# ADCIN_ACcoupled_TCM1-83X.net
KiCad netlist of a schematic drawn in Altium Designer
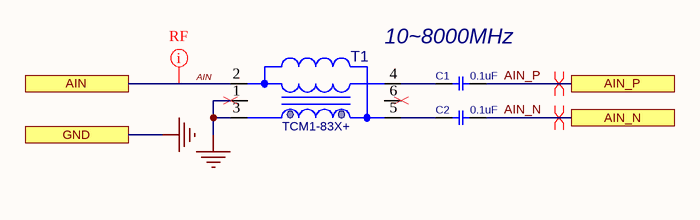
[diagram p0: ADCIN_ACcoupled_TCM1-83X+.SchDoc]

(export (version "E")
  (design (tool "Eeschema 10.0.6"))
  (components
    (comp (ref "C1")
      (value "0.1uF")
      (footprint "C0402")
      (description "CAP, MLCC, 100nF, 50V, X7R, 10%, 0402C")
      (fields (field (name "MANF_P#") "UMK105B7104KVHF") (field (name "MANF") "Taiyo Yuden"))
      (libsource (lib "mlcc_smd_passive") (part "CAP_SMD_MLCC_100n50T"))
    )
    (comp (ref "C2")
      (value "0.1uF")
      (footprint "C0402")
      (description "CAP, MLCC, 100nF, 50V, X7R, 10%, 0402C")
      (fields (field (name "MANF_P#") "UMK105B7104KVHF") (field (name "MANF") "Taiyo Yuden"))
      (libsource (lib "mlcc_smd_passive") (part "CAP_SMD_MLCC_100n50T"))
    )
    (comp (ref "T1")
      (value "TCM1-83X+")
      (footprint "TRNS127_6_S380CW")
      (description "RF Transformer, 1:1, 50Ohm, 10~8000MHz")
      (fields (field (name "MANF") "Mini-Circuit"))
      (libsource (lib "transformer_rf") (part "TCM1-83X+"))
    )
  )
  (nets
    (net (code "1") (name "/AIN") (class "Default")
      (node (ref "T1") (pin "2") (pinfunction "PRI_2") (pintype "passive"))
    )
    (net (code "2") (name "/AIN_N") (class "Default")
      (node (ref "C2") (pin "2") (pinfunction "2_2") (pintype "passive"))
    )
    (net (code "3") (name "/AIN_P") (class "Default")
      (node (ref "C1") (pin "2") (pinfunction "2_2") (pintype "passive"))
    )
    (net (code "4") (name "GND") (class "Default")
      (node (ref "T1") (pin "1") (pinfunction "NC_1") (pintype "passive"))
      (node (ref "T1") (pin "3") (pinfunction "PRI._3") (pintype "passive"))
    )
    (net (code "5") (name "Net-(C2-Pad1)") (class "Default")
      (node (ref "C2") (pin "1") (pinfunction "1_1") (pintype "passive"))
      (node (ref "T1") (pin "5") (pinfunction "NC_5") (pintype "passive"))
    )
    (net (code "6") (name "Net-(T1-SEC)") (class "Default")
      (node (ref "C1") (pin "1") (pinfunction "1_1") (pintype "passive"))
      (node (ref "T1") (pin "4") (pinfunction "SEC_4") (pintype "passive"))
    )
    (net (code "7") (name "unconnected-(T1-SEC.-Pad6)") (class "Default")
      (node (ref "T1") (pin "6") (pinfunction "SEC._6") (pintype "passive"))
    )
  )
)
